# V1_1.net
KiCad netlist of a schematic drawn in Altium Designer
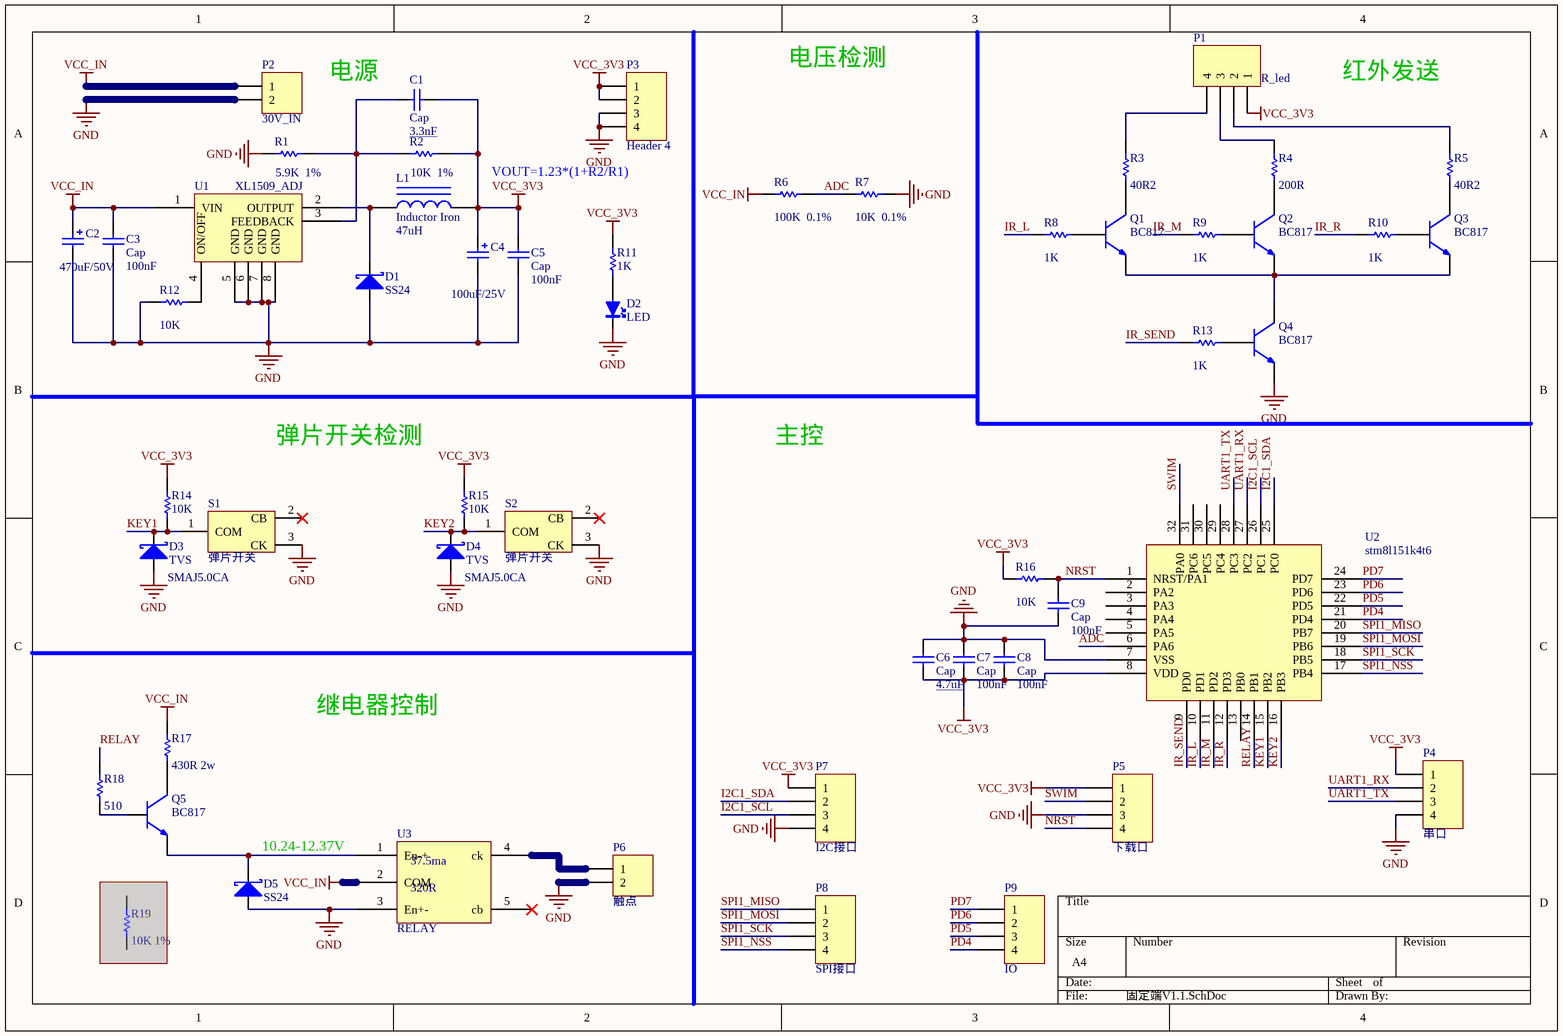
[diagram p0: 固定端V1.1.SchDoc]

(export (version "E")
  (design (tool "Eeschema 10.0.6"))
  (components
    (comp (ref "C1")
      (value "Cap")
      (footprint "C0603")
      (description "Capacitor")
      (fields (field (name "ALTIUM_VALUE") "3.3nF") (field (name "PUBLISHER") "Altium Limited"))
      (libsource (lib "boocax_schlib-20171017-1-dkw") (part "Cap"))
    )
    (comp (ref "C2")
      (value "470uF/50V")
      (footprint "CTH-R5-D5")
      (description "Polarized Capacitor (Radial)")
      (fields (field (name "Comment") "Cap Pol1") (field (name "PUBLISHER") "Altium Limited"))
      (libsource (lib "boocax_schlib") (part "Cap Pol1"))
    )
    (comp (ref "C3")
      (value "Cap")
      (footprint "C0603")
      (description "Capacitor")
      (fields (field (name "ALTIUM_VALUE") "100nF") (field (name "PUBLISHER") "Altium Limited"))
      (libsource (lib "boocax_schlib-20171017-1-dkw") (part "Cap"))
    )
    (comp (ref "C4")
      (value "100uF/25V")
      (footprint "CTH-R3-D2.54")
      (description "Polarized Capacitor (Radial)")
      (fields (field (name "Comment") "Cap Pol1") (field (name "PUBLISHER") "Altium Limited"))
      (libsource (lib "boocax_schlib") (part "Cap Pol1"))
    )
    (comp (ref "C5")
      (value "Cap")
      (footprint "C0603")
      (description "Capacitor")
      (fields (field (name "ALTIUM_VALUE") "100nF") (field (name "PUBLISHER") "Altium Limited"))
      (libsource (lib "boocax_schlib-20171017-1-dkw") (part "Cap"))
    )
    (comp (ref "C6")
      (value "Cap")
      (footprint "C0805")
      (description "Capacitor")
      (fields (field (name "ALTIUM_VALUE") "4.7uF") (field (name "PUBLISHER") "Altium Limited"))
      (libsource (lib "boocax_schlib-20171017-1-dkw") (part "Cap"))
    )
    (comp (ref "C7")
      (value "Cap")
      (footprint "C0603")
      (description "Capacitor")
      (fields (field (name "ALTIUM_VALUE") "100nF") (field (name "PUBLISHER") "Altium Limited"))
      (libsource (lib "boocax_schlib-20171017-1-dkw") (part "Cap"))
    )
    (comp (ref "C8")
      (value "Cap")
      (footprint "C0603")
      (description "Capacitor")
      (fields (field (name "ALTIUM_VALUE") "100nF") (field (name "PUBLISHER") "Altium Limited"))
      (libsource (lib "boocax_schlib-20171017-1-dkw") (part "Cap"))
    )
    (comp (ref "C9")
      (value "Cap")
      (footprint "C0603")
      (description "Capacitor")
      (fields (field (name "ALTIUM_VALUE") "100nF") (field (name "PUBLISHER") "Altium Limited"))
      (libsource (lib "boocax_schlib-20171017-1-dkw") (part "Cap"))
    )
    (comp (ref "D1")
      (value "SS24")
      (footprint "D-SMA")
      (description "肖特基二极管")
      (fields (field (name "Comment") "Diode-Schottky") (field (name "PUBLISHER") "Altium Limited"))
      (libsource (lib "boocax_schlib-20171017-1-dkw") (part "Diode-Schottky"))
    )
    (comp (ref "D2")
      (value "LED")
      (footprint "LED0805")
      (libsource (lib "boocax_schlib-20171017-1-dkw") (part "LED"))
    )
    (comp (ref "D3")
      (value "TVS")
      (footprint "D-SMA")
      (description "tvs瞬态抑制二极管")
      (fields (field (name "ALTIUM_VALUE") "SMAJ5.0CA"))
      (libsource (lib "boocax_schlib-20171017-1-dkw") (part "Diode-TVS"))
    )
    (comp (ref "D4")
      (value "TVS")
      (footprint "D-SMA")
      (description "tvs瞬态抑制二极管")
      (fields (field (name "ALTIUM_VALUE") "SMAJ5.0CA"))
      (libsource (lib "boocax_schlib-20171017-1-dkw") (part "Diode-TVS"))
    )
    (comp (ref "D5")
      (value "SS24")
      (footprint "D-SMA")
      (description "肖特基二极管")
      (fields (field (name "Comment") "Diode-Schottky") (field (name "PUBLISHER") "Altium Limited"))
      (libsource (lib "boocax_schlib-20171017-1-dkw") (part "Diode-Schottky"))
    )
    (comp (ref "L1")
      (value "Inductor Iron")
      (footprint "L-SMT-7257")
      (description "Magnetic-Core Inductor")
      (fields (field (name "ALTIUM_VALUE") "47uH") (field (name "PUBLISHER") "Altium Limited"))
      (libsource (lib "boocax_schlib-20171017-1-dkw") (part "Inductor Iron"))
    )
    (comp (ref "P1")
      (value "R_led")
      (footprint "XH2.54-4P")
      (description "Header, 4-Pin")
      (fields (field (name "PUBLISHER") "Altium Limited"))
      (libsource (lib "Miscellaneous Connectors") (part "Header 4"))
    )
    (comp (ref "P2")
      (value "30V_IN")
      (footprint "KF103-2p-5.08mm")
      (description "Header, 2-Pin")
      (fields (field (name "PUBLISHER") "Altium Limited"))
      (libsource (lib "Miscellaneous Connectors") (part "Header 2"))
    )
    (comp (ref "P3")
      (value "Header 4")
      (footprint "HDR1X4")
      (description "Header, 4-Pin")
      (fields (field (name "PUBLISHER") "Altium Limited"))
      (libsource (lib "Miscellaneous Connectors") (part "Header 4"))
    )
    (comp (ref "P4")
      (value "串口")
      (footprint "XH2.54-4P")
      (description "HEADER-4")
      (libsource (lib "常用元件库") (part "H4"))
    )
    (comp (ref "P5")
      (value "下载口")
      (footprint "HDR1X4")
      (description "HEADER-4")
      (libsource (lib "常用元件库") (part "H4"))
    )
    (comp (ref "P6")
      (value "触点")
      (footprint "KF103-2p-5.08mm")
      (description "Header, 2-Pin")
      (fields (field (name "PUBLISHER") "Altium Limited"))
      (libsource (lib "Miscellaneous Connectors") (part "Header 2"))
    )
    (comp (ref "P7")
      (value "I2C接口")
      (footprint "HDR1X4")
      (description "HEADER-4")
      (libsource (lib "常用元件库") (part "H4"))
    )
    (comp (ref "P8")
      (value "SPI接口")
      (footprint "HDR1X4")
      (description "HEADER-4")
      (libsource (lib "常用元件库") (part "H4"))
    )
    (comp (ref "P9")
      (value "IO")
      (footprint "HDR1X4")
      (description "HEADER-4")
      (libsource (lib "常用元件库") (part "H4"))
    )
    (comp (ref "Q1")
      (value "BC817")
      (footprint "SOT23-3")
      (description "NPN 45V 功耗 310mW")
      (libsource (lib "Schlib1") (part "mNPN"))
    )
    (comp (ref "Q2")
      (value "BC817")
      (footprint "SOT23-3")
      (description "NPN 45V 功耗 310mW")
      (libsource (lib "Schlib1") (part "mNPN"))
    )
    (comp (ref "Q3")
      (value "BC817")
      (footprint "SOT23-3")
      (description "NPN 45V 功耗 310mW")
      (libsource (lib "Schlib1") (part "mNPN"))
    )
    (comp (ref "Q4")
      (value "BC817")
      (footprint "SOT23-3")
      (description "NPN 45V 功耗 310mW")
      (libsource (lib "Schlib1") (part "mNPN"))
    )
    (comp (ref "Q5")
      (value "BC817")
      (footprint "SOT23-3")
      (description "NPN 45V 功耗 310mW")
      (libsource (lib "Schlib1") (part "mNPN"))
    )
    (comp (ref "R1")
      (value "5.9K  1%")
      (footprint "R0603")
      (description "Resistor")
      (fields (field (name "Comment") "Res1") (field (name "PUBLISHER") "Altium Limited"))
      (libsource (lib "boocax_schlib-20171017-1-dkw") (part "Res1"))
    )
    (comp (ref "R2")
      (value "10K  1%")
      (footprint "R0603")
      (description "Resistor")
      (fields (field (name "Comment") "Res1") (field (name "PUBLISHER") "Altium Limited"))
      (libsource (lib "boocax_schlib-20171017-1-dkw") (part "Res1"))
    )
    (comp (ref "R3")
      (value "40R2")
      (footprint "R0603")
      (description "Resistor")
      (fields (field (name "Comment") "Res1") (field (name "PUBLISHER") "Altium Limited"))
      (libsource (lib "boocax_schlib-20171017-1-dkw") (part "Res1"))
    )
    (comp (ref "R4")
      (value "200R")
      (footprint "R0603")
      (description "Resistor")
      (fields (field (name "Comment") "Res1") (field (name "PUBLISHER") "Altium Limited"))
      (libsource (lib "boocax_schlib-20171017-1-dkw") (part "Res1"))
    )
    (comp (ref "R5")
      (value "40R2")
      (footprint "R0603")
      (description "Resistor")
      (fields (field (name "Comment") "Res1") (field (name "PUBLISHER") "Altium Limited"))
      (libsource (lib "boocax_schlib-20171017-1-dkw") (part "Res1"))
    )
    (comp (ref "R6")
      (value "100K  0.1%")
      (footprint "R0603")
      (description "Resistor")
      (fields (field (name "Comment") "Res1") (field (name "PUBLISHER") "Altium Limited"))
      (libsource (lib "boocax_schlib-20171017-1-dkw") (part "Res1"))
    )
    (comp (ref "R7")
      (value "10K  0.1%")
      (footprint "R0603")
      (description "Resistor")
      (fields (field (name "Comment") "Res1") (field (name "PUBLISHER") "Altium Limited"))
      (libsource (lib "boocax_schlib-20171017-1-dkw") (part "Res1"))
    )
    (comp (ref "R8")
      (value "1K")
      (footprint "R0603")
      (description "Resistor")
      (fields (field (name "Comment") "Res1") (field (name "PUBLISHER") "Altium Limited"))
      (libsource (lib "boocax_schlib-20171017-1-dkw") (part "Res1"))
    )
    (comp (ref "R9")
      (value "1K")
      (footprint "R0603")
      (description "Resistor")
      (fields (field (name "Comment") "Res1") (field (name "PUBLISHER") "Altium Limited"))
      (libsource (lib "boocax_schlib-20171017-1-dkw") (part "Res1"))
    )
    (comp (ref "R10")
      (value "1K")
      (footprint "R0603")
      (description "Resistor")
      (fields (field (name "Comment") "Res1") (field (name "PUBLISHER") "Altium Limited"))
      (libsource (lib "boocax_schlib-20171017-1-dkw") (part "Res1"))
    )
    (comp (ref "R11")
      (value "1K")
      (footprint "R0603")
      (description "Resistor")
      (fields (field (name "Comment") "Res1") (field (name "PUBLISHER") "Altium Limited"))
      (libsource (lib "boocax_schlib-20171017-1-dkw") (part "Res1"))
    )
    (comp (ref "R12")
      (value "10K")
      (footprint "R0603")
      (description "Resistor")
      (fields (field (name "Comment") "Res1") (field (name "PUBLISHER") "Altium Limited"))
      (libsource (lib "boocax_schlib-20171017-1-dkw") (part "Res1"))
    )
    (comp (ref "R13")
      (value "1K")
      (footprint "R0603")
      (description "Resistor")
      (fields (field (name "Comment") "Res1") (field (name "PUBLISHER") "Altium Limited"))
      (libsource (lib "boocax_schlib-20171017-1-dkw") (part "Res1"))
    )
    (comp (ref "R14")
      (value "10K")
      (footprint "R0603")
      (description "Resistor")
      (fields (field (name "Comment") "Res1") (field (name "PUBLISHER") "Altium Limited"))
      (libsource (lib "boocax_schlib-20171017-1-dkw") (part "Res1"))
    )
    (comp (ref "R15")
      (value "10K")
      (footprint "R0603")
      (description "Resistor")
      (fields (field (name "Comment") "Res1") (field (name "PUBLISHER") "Altium Limited"))
      (libsource (lib "boocax_schlib-20171017-1-dkw") (part "Res1"))
    )
    (comp (ref "R16")
      (value "10K")
      (footprint "R0603")
      (description "Resistor")
      (fields (field (name "Comment") "Res1") (field (name "PUBLISHER") "Altium Limited"))
      (libsource (lib "boocax_schlib-20171017-1-dkw") (part "Res1"))
    )
    (comp (ref "R17")
      (value "430R 2w")
      (footprint "AXIAL-0.4")
      (description "Resistor")
      (fields (field (name "Comment") "Res1") (field (name "PUBLISHER") "Altium Limited"))
      (libsource (lib "boocax_schlib-20171017-1-dkw") (part "Res1"))
    )
    (comp (ref "R18")
      (value "510")
      (footprint "R0603")
      (description "Resistor")
      (fields (field (name "Comment") "Res1") (field (name "PUBLISHER") "Altium Limited"))
      (libsource (lib "boocax_schlib-20171017-1-dkw") (part "Res1"))
    )
    (comp (ref "R19")
      (value "10K 1%")
      (footprint "AXIAL-0.4")
      (description "Resistor")
      (fields (field (name "Comment") "Res1") (field (name "PUBLISHER") "Altium Limited"))
      (libsource (lib "boocax_schlib-20171017-1-dkw") (part "Res1"))
    )
    (comp (ref "S1")
      (value "弹片开关")
      (footprint "SW_limit_3pin")
      (description "3脚弹片限位开关")
      (libsource (lib "boocax_schlib-20171017-1-dkw") (part "SW_limit_3pin"))
    )
    (comp (ref "S2")
      (value "弹片开关")
      (footprint "SW_limit_3pin")
      (description "3脚弹片限位开关")
      (libsource (lib "boocax_schlib-20171017-1-dkw") (part "SW_limit_3pin"))
    )
    (comp (ref "U1")
      (value "XL1509_ADJ")
      (footprint "SOP8")
      (description "BUCK DCDC")
      (libsource (lib "boocax_schlib-20171017-1-dkw") (part "XL1509"))
    )
    (comp (ref "U2")
      (value "stm8l151k4t6")
      (footprint "qfp32-32-0909a")
      (libsource (lib "boocax_schlib-20171017-1-dkw") (part "stm8l151k4t6"))
    )
    (comp (ref "U3")
      (value "RELAY")
      (footprint "relay-12v-5PIN")
      (description "5脚12V大功率继电器")
      (libsource (lib "boocax_schlib-20171017-1-dkw") (part "relay-5PIN"))
    )
  )
  (nets
    (net (code "1") (name "/ADC") (class "Default")
      (node (ref "R6") (pin "2") (pinfunction "2_2") (pintype "passive"))
      (node (ref "R7") (pin "1") (pinfunction "1_1") (pintype "passive"))
      (node (ref "U2") (pin "6") (pinfunction "PA6_6") (pintype "passive"))
    )
    (net (code "2") (name "/I2C1_SCL") (class "Default")
      (node (ref "P7") (pin "3") (pinfunction "3_3") (pintype "passive"))
      (node (ref "U2") (pin "26") (pinfunction "PC1_26") (pintype "passive"))
    )
    (net (code "3") (name "/I2C1_SDA") (class "Default")
      (node (ref "P7") (pin "2") (pinfunction "2_2") (pintype "passive"))
      (node (ref "U2") (pin "25") (pinfunction "PC0_25") (pintype "passive"))
    )
    (net (code "4") (name "/IR_L") (class "Default")
      (node (ref "R8") (pin "1") (pinfunction "1_1") (pintype "passive"))
      (node (ref "U2") (pin "10") (pinfunction "PD1_10") (pintype "passive"))
    )
    (net (code "5") (name "/IR_M") (class "Default")
      (node (ref "R9") (pin "1") (pinfunction "1_1") (pintype "passive"))
      (node (ref "U2") (pin "11") (pinfunction "PD2_11") (pintype "passive"))
    )
    (net (code "6") (name "/IR_R") (class "Default")
      (node (ref "R10") (pin "1") (pinfunction "1_1") (pintype "passive"))
      (node (ref "U2") (pin "12") (pinfunction "PD3_12") (pintype "passive"))
    )
    (net (code "7") (name "/IR_SEND") (class "Default")
      (node (ref "R13") (pin "1") (pinfunction "1_1") (pintype "passive"))
      (node (ref "U2") (pin "9") (pinfunction "PD0_9") (pintype "passive"))
    )
    (net (code "8") (name "/KEY1") (class "Default")
      (node (ref "D3") (pin "2") (pinfunction "K_2") (pintype "passive"))
      (node (ref "R14") (pin "1") (pinfunction "1_1") (pintype "passive"))
      (node (ref "S1") (pin "1") (pinfunction "COM_1") (pintype "passive"))
      (node (ref "U2") (pin "15") (pinfunction "PB2_15") (pintype "passive"))
    )
    (net (code "9") (name "/KEY2") (class "Default")
      (node (ref "D4") (pin "2") (pinfunction "K_2") (pintype "passive"))
      (node (ref "R15") (pin "1") (pinfunction "1_1") (pintype "passive"))
      (node (ref "S2") (pin "1") (pinfunction "COM_1") (pintype "passive"))
      (node (ref "U2") (pin "16") (pinfunction "PB3_16") (pintype "passive"))
    )
    (net (code "10") (name "/NRST") (class "Default")
      (node (ref "C9") (pin "2") (pinfunction "2_2") (pintype "passive"))
      (node (ref "P5") (pin "4") (pinfunction "4_4") (pintype "passive"))
      (node (ref "R16") (pin "2") (pinfunction "2_2") (pintype "passive"))
      (node (ref "U2") (pin "1") (pinfunction "NRST/PA1_1") (pintype "passive"))
    )
    (net (code "11") (name "/PD4") (class "Default")
      (node (ref "P9") (pin "4") (pinfunction "4_4") (pintype "passive"))
      (node (ref "U2") (pin "21") (pinfunction "PD4_21") (pintype "passive"))
    )
    (net (code "12") (name "/PD5") (class "Default")
      (node (ref "P9") (pin "3") (pinfunction "3_3") (pintype "passive"))
      (node (ref "U2") (pin "22") (pinfunction "PD5_22") (pintype "passive"))
    )
    (net (code "13") (name "/PD6") (class "Default")
      (node (ref "P9") (pin "2") (pinfunction "2_2") (pintype "passive"))
      (node (ref "U2") (pin "23") (pinfunction "PD6_23") (pintype "passive"))
    )
    (net (code "14") (name "/PD7") (class "Default")
      (node (ref "P9") (pin "1") (pinfunction "1_1") (pintype "passive"))
      (node (ref "U2") (pin "24") (pinfunction "PD7_24") (pintype "passive"))
    )
    (net (code "15") (name "/RELAY") (class "Default")
      (node (ref "R18") (pin "1") (pinfunction "1_1") (pintype "passive"))
      (node (ref "U2") (pin "14") (pinfunction "PB1_14") (pintype "passive"))
    )
    (net (code "16") (name "/SPI1_MISO") (class "Default")
      (node (ref "P8") (pin "1") (pinfunction "1_1") (pintype "passive"))
      (node (ref "U2") (pin "20") (pinfunction "PB7_20") (pintype "passive"))
    )
    (net (code "17") (name "/SPI1_MOSI") (class "Default")
      (node (ref "P8") (pin "2") (pinfunction "2_2") (pintype "passive"))
      (node (ref "U2") (pin "19") (pinfunction "PB6_19") (pintype "passive"))
    )
    (net (code "18") (name "/SPI1_NSS") (class "Default")
      (node (ref "P8") (pin "4") (pinfunction "4_4") (pintype "passive"))
      (node (ref "U2") (pin "17") (pinfunction "PB4_17") (pintype "passive"))
    )
    (net (code "19") (name "/SPI1_SCK") (class "Default")
      (node (ref "P8") (pin "3") (pinfunction "3_3") (pintype "passive"))
      (node (ref "U2") (pin "18") (pinfunction "PB5_18") (pintype "passive"))
    )
    (net (code "20") (name "/SWIM") (class "Default")
      (node (ref "P5") (pin "2") (pinfunction "2_2") (pintype "passive"))
      (node (ref "U2") (pin "32") (pinfunction "PA0_32") (pintype "passive"))
    )
    (net (code "21") (name "/UART1_RX") (class "Default")
      (node (ref "P4") (pin "2") (pinfunction "2_2") (pintype "passive"))
      (node (ref "U2") (pin "27") (pinfunction "PC2_27") (pintype "passive"))
    )
    (net (code "22") (name "/UART1_TX") (class "Default")
      (node (ref "P4") (pin "3") (pinfunction "3_3") (pintype "passive"))
      (node (ref "U2") (pin "28") (pinfunction "PC3_28") (pintype "passive"))
    )
    (net (code "23") (name "GND") (class "Default")
      (node (ref "C2") (pin "2") (pinfunction "2_2") (pintype "passive"))
      (node (ref "C3") (pin "1") (pinfunction "1_1") (pintype "passive"))
      (node (ref "C4") (pin "2") (pinfunction "2_2") (pintype "passive"))
      (node (ref "C5") (pin "1") (pinfunction "1_1") (pintype "passive"))
      (node (ref "C6") (pin "2") (pinfunction "2_2") (pintype "passive"))
      (node (ref "C7") (pin "2") (pinfunction "2_2") (pintype "passive"))
      (node (ref "C8") (pin "2") (pinfunction "2_2") (pintype "passive"))
      (node (ref "C9") (pin "1") (pinfunction "1_1") (pintype "passive"))
      (node (ref "D1") (pin "1") (pinfunction "A_1") (pintype "passive"))
      (node (ref "D2") (pin "2") (pinfunction "K_2") (pintype "passive"))
      (node (ref "D3") (pin "1") (pinfunction "A_1") (pintype "passive"))
      (node (ref "D4") (pin "1") (pinfunction "A_1") (pintype "passive"))
      (node (ref "D5") (pin "1") (pinfunction "A_1") (pintype "passive"))
      (node (ref "P2") (pin "2") (pinfunction "2_2") (pintype "passive"))
      (node (ref "P3") (pin "3") (pinfunction "3_3") (pintype "passive"))
      (node (ref "P3") (pin "4") (pinfunction "4_4") (pintype "passive"))
      (node (ref "P4") (pin "4") (pinfunction "4_4") (pintype "passive"))
      (node (ref "P5") (pin "3") (pinfunction "3_3") (pintype "passive"))
      (node (ref "P6") (pin "2") (pinfunction "2_2") (pintype "passive"))
      (node (ref "P7") (pin "4") (pinfunction "4_4") (pintype "passive"))
      (node (ref "Q4") (pin "2") (pinfunction "E_2") (pintype "passive"))
      (node (ref "R1") (pin "1") (pinfunction "1_1") (pintype "passive"))
      (node (ref "R12") (pin "2") (pinfunction "2_2") (pintype "passive"))
      (node (ref "R7") (pin "2") (pinfunction "2_2") (pintype "passive"))
      (node (ref "S1") (pin "3") (pinfunction "CK_3") (pintype "passive"))
      (node (ref "S2") (pin "3") (pinfunction "CK_3") (pintype "passive"))
      (node (ref "U1") (pin "5") (pinfunction "GND_5") (pintype "passive"))
      (node (ref "U1") (pin "6") (pinfunction "GND_6") (pintype "passive"))
      (node (ref "U1") (pin "7") (pinfunction "GND_7") (pintype "passive"))
      (node (ref "U1") (pin "8") (pinfunction "GND_8") (pintype "passive"))
      (node (ref "U2") (pin "7") (pinfunction "VSS_7") (pintype "passive"))
      (node (ref "U3") (pin "3") (pinfunction "En+-_3") (pintype "passive"))
    )
    (net (code "24") (name "Net-(D1-K)") (class "Default")
      (node (ref "D1") (pin "2") (pinfunction "K_2") (pintype "passive"))
      (node (ref "L1") (pin "1") (pinfunction "1_1") (pintype "passive"))
      (node (ref "U1") (pin "2") (pinfunction "OUTPUT_2") (pintype "passive"))
    )
    (net (code "25") (name "Net-(D2-A)") (class "Default")
      (node (ref "D2") (pin "1") (pinfunction "A_1") (pintype "passive"))
      (node (ref "R11") (pin "2") (pinfunction "2_2") (pintype "passive"))
    )
    (net (code "26") (name "Net-(D5-K)") (class "Default")
      (node (ref "D5") (pin "2") (pinfunction "K_2") (pintype "passive"))
      (node (ref "Q5") (pin "2") (pinfunction "E_2") (pintype "passive"))
      (node (ref "U3") (pin "1") (pinfunction "En-+_1") (pintype "passive"))
    )
    (net (code "27") (name "Net-(P1-Pad2)") (class "Default")
      (node (ref "P1") (pin "2") (pinfunction "2_2") (pintype "passive"))
      (node (ref "R5") (pin "2") (pinfunction "2_2") (pintype "passive"))
    )
    (net (code "28") (name "Net-(P1-Pad3)") (class "Default")
      (node (ref "P1") (pin "3") (pinfunction "3_3") (pintype "passive"))
      (node (ref "R4") (pin "2") (pinfunction "2_2") (pintype "passive"))
    )
    (net (code "29") (name "Net-(P1-Pad4)") (class "Default")
      (node (ref "P1") (pin "4") (pinfunction "4_4") (pintype "passive"))
      (node (ref "R3") (pin "2") (pinfunction "2_2") (pintype "passive"))
    )
    (net (code "30") (name "Net-(Q1-B)") (class "Default")
      (node (ref "Q1") (pin "1") (pinfunction "B_1") (pintype "passive"))
      (node (ref "R8") (pin "2") (pinfunction "2_2") (pintype "passive"))
    )
    (net (code "31") (name "Net-(Q1-C)") (class "Default")
      (node (ref "Q1") (pin "3") (pinfunction "C_3") (pintype "passive"))
      (node (ref "R3") (pin "1") (pinfunction "1_1") (pintype "passive"))
    )
    (net (code "32") (name "Net-(Q1-E)") (class "Default")
      (node (ref "Q1") (pin "2") (pinfunction "E_2") (pintype "passive"))
      (node (ref "Q2") (pin "2") (pinfunction "E_2") (pintype "passive"))
      (node (ref "Q3") (pin "2") (pinfunction "E_2") (pintype "passive"))
      (node (ref "Q4") (pin "3") (pinfunction "C_3") (pintype "passive"))
    )
    (net (code "33") (name "Net-(Q2-B)") (class "Default")
      (node (ref "Q2") (pin "1") (pinfunction "B_1") (pintype "passive"))
      (node (ref "R9") (pin "2") (pinfunction "2_2") (pintype "passive"))
    )
    (net (code "34") (name "Net-(Q2-C)") (class "Default")
      (node (ref "Q2") (pin "3") (pinfunction "C_3") (pintype "passive"))
      (node (ref "R4") (pin "1") (pinfunction "1_1") (pintype "passive"))
    )
    (net (code "35") (name "Net-(Q3-B)") (class "Default")
      (node (ref "Q3") (pin "1") (pinfunction "B_1") (pintype "passive"))
      (node (ref "R10") (pin "2") (pinfunction "2_2") (pintype "passive"))
    )
    (net (code "36") (name "Net-(Q3-C)") (class "Default")
      (node (ref "Q3") (pin "3") (pinfunction "C_3") (pintype "passive"))
      (node (ref "R5") (pin "1") (pinfunction "1_1") (pintype "passive"))
    )
    (net (code "37") (name "Net-(Q4-B)") (class "Default")
      (node (ref "Q4") (pin "1") (pinfunction "B_1") (pintype "passive"))
      (node (ref "R13") (pin "2") (pinfunction "2_2") (pintype "passive"))
    )
    (net (code "38") (name "Net-(Q5-B)") (class "Default")
      (node (ref "Q5") (pin "1") (pinfunction "B_1") (pintype "passive"))
      (node (ref "R18") (pin "2") (pinfunction "2_2") (pintype "passive"))
    )
    (net (code "39") (name "Net-(Q5-C)") (class "Default")
      (node (ref "Q5") (pin "3") (pinfunction "C_3") (pintype "passive"))
      (node (ref "R17") (pin "2") (pinfunction "2_2") (pintype "passive"))
    )
    (net (code "40") (name "Net-(U1-FEEDBACK)") (class "Default")
      (node (ref "C1") (pin "2") (pinfunction "2_2") (pintype "passive"))
      (node (ref "R1") (pin "2") (pinfunction "2_2") (pintype "passive"))
      (node (ref "R2") (pin "1") (pinfunction "1_1") (pintype "passive"))
      (node (ref "U1") (pin "3") (pinfunction "FEEDBACK_3") (pintype "passive"))
    )
    (net (code "41") (name "Net-(U1-ON{slash}OFF)") (class "Default")
      (node (ref "R12") (pin "1") (pinfunction "1_1") (pintype "passive"))
      (node (ref "U1") (pin "4") (pinfunction "ON/OFF_4") (pintype "passive"))
    )
    (net (code "42") (name "Net-(U3-ck)") (class "Default")
      (node (ref "P6") (pin "1") (pinfunction "1_1") (pintype "passive"))
      (node (ref "U3") (pin "4") (pinfunction "ck_4") (pintype "passive"))
    )
    (net (code "43") (name "VCC_3V3") (class "Default")
      (node (ref "C1") (pin "1") (pinfunction "1_1") (pintype "passive"))
      (node (ref "C4") (pin "1") (pinfunction "1_1") (pintype "passive"))
      (node (ref "C5") (pin "2") (pinfunction "2_2") (pintype "passive"))
      (node (ref "C6") (pin "1") (pinfunction "1_1") (pintype "passive"))
      (node (ref "C7") (pin "1") (pinfunction "1_1") (pintype "passive"))
      (node (ref "C8") (pin "1") (pinfunction "1_1") (pintype "passive"))
      (node (ref "L1") (pin "2") (pinfunction "2_2") (pintype "passive"))
      (node (ref "P1") (pin "1") (pinfunction "1_1") (pintype "passive"))
      (node (ref "P3") (pin "1") (pinfunction "1_1") (pintype "passive"))
      (node (ref "P3") (pin "2") (pinfunction "2_2") (pintype "passive"))
      (node (ref "P4") (pin "1") (pinfunction "1_1") (pintype "passive"))
      (node (ref "P5") (pin "1") (pinfunction "1_1") (pintype "passive"))
      (node (ref "P7") (pin "1") (pinfunction "1_1") (pintype "passive"))
      (node (ref "R11") (pin "1") (pinfunction "1_1") (pintype "passive"))
      (node (ref "R14") (pin "2") (pinfunction "2_2") (pintype "passive"))
      (node (ref "R15") (pin "2") (pinfunction "2_2") (pintype "passive"))
      (node (ref "R16") (pin "1") (pinfunction "1_1") (pintype "passive"))
      (node (ref "R2") (pin "2") (pinfunction "2_2") (pintype "passive"))
      (node (ref "U2") (pin "8") (pinfunction "VDD_8") (pintype "passive"))
    )
    (net (code "44") (name "VCC_IN") (class "Default")
      (node (ref "C2") (pin "1") (pinfunction "1_1") (pintype "passive"))
      (node (ref "C3") (pin "2") (pinfunction "2_2") (pintype "passive"))
      (node (ref "P2") (pin "1") (pinfunction "1_1") (pintype "passive"))
      (node (ref "R17") (pin "1") (pinfunction "1_1") (pintype "passive"))
      (node (ref "R6") (pin "1") (pinfunction "1_1") (pintype "passive"))
      (node (ref "U1") (pin "1") (pinfunction "VIN_1") (pintype "passive"))
      (node (ref "U3") (pin "2") (pinfunction "COM_2") (pintype "passive"))
    )
    (net (code "45") (name "unconnected-(R19-Pad1)") (class "Default")
      (node (ref "R19") (pin "1") (pinfunction "1_1") (pintype "passive"))
    )
    (net (code "46") (name "unconnected-(R19-Pad2)") (class "Default")
      (node (ref "R19") (pin "2") (pinfunction "2_2") (pintype "passive"))
    )
    (net (code "47") (name "unconnected-(S1-CB-Pad2)") (class "Default")
      (node (ref "S1") (pin "2") (pinfunction "CB_2") (pintype "passive+no_connect"))
    )
    (net (code "48") (name "unconnected-(S2-CB-Pad2)") (class "Default")
      (node (ref "S2") (pin "2") (pinfunction "CB_2") (pintype "passive+no_connect"))
    )
    (net (code "49") (name "unconnected-(U2-PA2-Pad2)") (class "Default")
      (node (ref "U2") (pin "2") (pinfunction "PA2_2") (pintype "passive"))
    )
    (net (code "50") (name "unconnected-(U2-PA3-Pad3)") (class "Default")
      (node (ref "U2") (pin "3") (pinfunction "PA3_3") (pintype "passive"))
    )
    (net (code "51") (name "unconnected-(U2-PA4-Pad4)") (class "Default")
      (node (ref "U2") (pin "4") (pinfunction "PA4_4") (pintype "passive"))
    )
    (net (code "52") (name "unconnected-(U2-PA5-Pad5)") (class "Default")
      (node (ref "U2") (pin "5") (pinfunction "PA5_5") (pintype "passive"))
    )
    (net (code "53") (name "unconnected-(U2-PB0-Pad13)") (class "Default")
      (node (ref "U2") (pin "13") (pinfunction "PB0_13") (pintype "passive"))
    )
    (net (code "54") (name "unconnected-(U2-PC4-Pad29)") (class "Default")
      (node (ref "U2") (pin "29") (pinfunction "PC4_29") (pintype "passive"))
    )
    (net (code "55") (name "unconnected-(U2-PC5-Pad30)") (class "Default")
      (node (ref "U2") (pin "30") (pinfunction "PC5_30") (pintype "passive"))
    )
    (net (code "56") (name "unconnected-(U2-PC6-Pad31)") (class "Default")
      (node (ref "U2") (pin "31") (pinfunction "PC6_31") (pintype "passive"))
    )
    (net (code "57") (name "unconnected-(U3-cb-Pad5)") (class "Default")
      (node (ref "U3") (pin "5") (pinfunction "cb_5") (pintype "passive+no_connect"))
    )
  )
)
